# Sheet1.net
KiCad netlist of a schematic drawn in Altium Designer
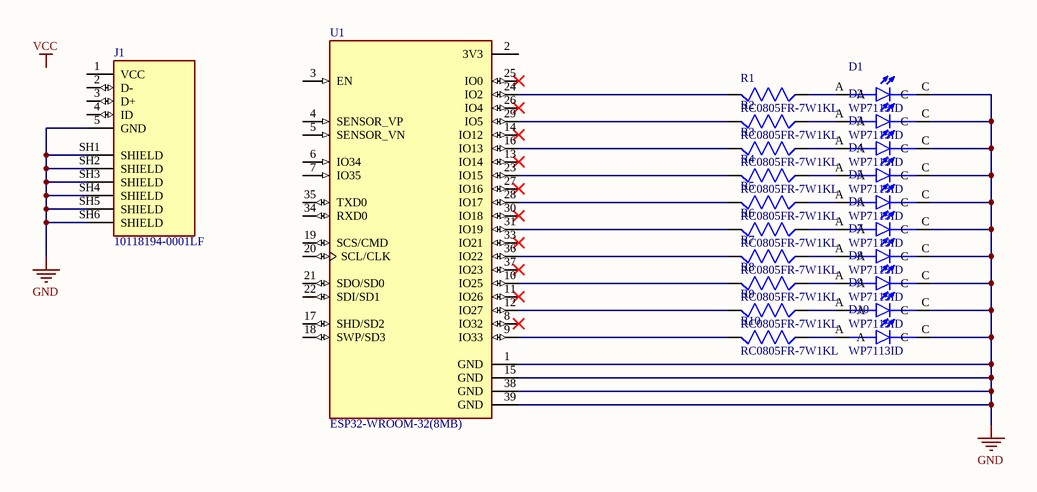
[diagram p0: Sheet1.SchDoc]

(export (version "E")
  (design (tool "Eeschema 10.0.6"))
  (components
    (comp (ref "D1")
      (value "WP7113ID")
      (footprint "LED_WP7113ID")
      (description "Red 617nm LED Indication - Discrete 2V Radial")
      (fields (field (name "MF") "Kingbright"))
      (libsource (lib "WP7113ID") (part "WP7113ID"))
    )
    (comp (ref "D2")
      (value "WP7113ID")
      (footprint "LED_WP7113ID")
      (description "Red 617nm LED Indication - Discrete 2V Radial")
      (fields (field (name "MF") "Kingbright"))
      (libsource (lib "WP7113ID") (part "WP7113ID"))
    )
    (comp (ref "D3")
      (value "WP7113ID")
      (footprint "LED_WP7113ID")
      (description "Red 617nm LED Indication - Discrete 2V Radial")
      (fields (field (name "MF") "Kingbright"))
      (libsource (lib "WP7113ID") (part "WP7113ID"))
    )
    (comp (ref "D4")
      (value "WP7113ID")
      (footprint "LED_WP7113ID")
      (description "Red 617nm LED Indication - Discrete 2V Radial")
      (fields (field (name "MF") "Kingbright"))
      (libsource (lib "WP7113ID") (part "WP7113ID"))
    )
    (comp (ref "D5")
      (value "WP7113ID")
      (footprint "LED_WP7113ID")
      (description "Red 617nm LED Indication - Discrete 2V Radial")
      (fields (field (name "MF") "Kingbright"))
      (libsource (lib "WP7113ID") (part "WP7113ID"))
    )
    (comp (ref "D6")
      (value "WP7113ID")
      (footprint "LED_WP7113ID")
      (description "Red 617nm LED Indication - Discrete 2V Radial")
      (fields (field (name "MF") "Kingbright"))
      (libsource (lib "WP7113ID") (part "WP7113ID"))
    )
    (comp (ref "D7")
      (value "WP7113ID")
      (footprint "LED_WP7113ID")
      (description "Red 617nm LED Indication - Discrete 2V Radial")
      (fields (field (name "MF") "Kingbright"))
      (libsource (lib "WP7113ID") (part "WP7113ID"))
    )
    (comp (ref "D8")
      (value "WP7113ID")
      (footprint "LED_WP7113ID")
      (description "Red 617nm LED Indication - Discrete 2V Radial")
      (fields (field (name "MF") "Kingbright"))
      (libsource (lib "WP7113ID") (part "WP7113ID"))
    )
    (comp (ref "D9")
      (value "WP7113ID")
      (footprint "LED_WP7113ID")
      (description "Red 617nm LED Indication - Discrete 2V Radial")
      (fields (field (name "MF") "Kingbright"))
      (libsource (lib "WP7113ID") (part "WP7113ID"))
    )
    (comp (ref "D10")
      (value "WP7113ID")
      (footprint "LED_WP7113ID")
      (description "Red 617nm LED Indication - Discrete 2V Radial")
      (fields (field (name "MF") "Kingbright"))
      (libsource (lib "WP7113ID") (part "WP7113ID"))
    )
    (comp (ref "J1")
      (value "10118194-0001LF")
      (footprint "AMPHENOL_10118194-0001LF")
      (description "Micro USB, Input Output Connectors, B TYPE RECEPTACLE with flange")
      (fields (field (name "MF") "Amphenol ICC"))
      (libsource (lib "10118194-0001LF") (part "10118194-0001LF"))
    )
    (comp (ref "R1")
      (value "RC0805FR-7W1KL")
      (footprint "RESC2012X60N")
      (libsource (lib "RC0805FR-7W1KL") (part "RC0805FR-7W1KL"))
    )
    (comp (ref "R2")
      (value "RC0805FR-7W1KL")
      (footprint "RESC2012X60N")
      (libsource (lib "RC0805FR-7W1KL") (part "RC0805FR-7W1KL"))
    )
    (comp (ref "R3")
      (value "RC0805FR-7W1KL")
      (footprint "RESC2012X60N")
      (libsource (lib "RC0805FR-7W1KL") (part "RC0805FR-7W1KL"))
    )
    (comp (ref "R4")
      (value "RC0805FR-7W1KL")
      (footprint "RESC2012X60N")
      (libsource (lib "RC0805FR-7W1KL") (part "RC0805FR-7W1KL"))
    )
    (comp (ref "R5")
      (value "RC0805FR-7W1KL")
      (footprint "RESC2012X60N")
      (libsource (lib "RC0805FR-7W1KL") (part "RC0805FR-7W1KL"))
    )
    (comp (ref "R6")
      (value "RC0805FR-7W1KL")
      (footprint "RESC2012X60N")
      (libsource (lib "RC0805FR-7W1KL") (part "RC0805FR-7W1KL"))
    )
    (comp (ref "R7")
      (value "RC0805FR-7W1KL")
      (footprint "RESC2012X60N")
      (libsource (lib "RC0805FR-7W1KL") (part "RC0805FR-7W1KL"))
    )
    (comp (ref "R8")
      (value "RC0805FR-7W1KL")
      (footprint "RESC2012X60N")
      (libsource (lib "RC0805FR-7W1KL") (part "RC0805FR-7W1KL"))
    )
    (comp (ref "R9")
      (value "RC0805FR-7W1KL")
      (footprint "RESC2012X60N")
      (libsource (lib "RC0805FR-7W1KL") (part "RC0805FR-7W1KL"))
    )
    (comp (ref "R10")
      (value "RC0805FR-7W1KL")
      (footprint "RESC2012X60N")
      (libsource (lib "RC0805FR-7W1KL") (part "RC0805FR-7W1KL"))
    )
    (comp (ref "U1")
      (value "ESP32-WROOM-32(8MB)")
      (footprint "MODULE_ESP32-WROOM-32(8MB)")
      (fields (field (name "MF") "Espressif Systems") (field (name "MP") "ESP32-WROOM-32 (8MB)"))
      (libsource (lib "ESP32-WROOM-32(8MB)") (part "ESP32-WROOM-32(8MB)"))
    )
  )
  (nets
    (net (code "1") (name "GND") (class "Default")
      (node (ref "D1") (pin "C") (pinfunction "C_C") (pintype "passive"))
      (node (ref "D10") (pin "C") (pinfunction "C_C") (pintype "passive"))
      (node (ref "D2") (pin "C") (pinfunction "C_C") (pintype "passive"))
      (node (ref "D3") (pin "C") (pinfunction "C_C") (pintype "passive"))
      (node (ref "D4") (pin "C") (pinfunction "C_C") (pintype "passive"))
      (node (ref "D5") (pin "C") (pinfunction "C_C") (pintype "passive"))
      (node (ref "D6") (pin "C") (pinfunction "C_C") (pintype "passive"))
      (node (ref "D7") (pin "C") (pinfunction "C_C") (pintype "passive"))
      (node (ref "D8") (pin "C") (pinfunction "C_C") (pintype "passive"))
      (node (ref "D9") (pin "C") (pinfunction "C_C") (pintype "passive"))
      (node (ref "J1") (pin "5") (pinfunction "GND_5") (pintype "power_in"))
      (node (ref "J1") (pin "SH1") (pinfunction "SHIELD_SH1") (pintype "passive"))
      (node (ref "J1") (pin "SH2") (pinfunction "SHIELD_SH2") (pintype "passive"))
      (node (ref "J1") (pin "SH3") (pinfunction "SHIELD_SH3") (pintype "passive"))
      (node (ref "J1") (pin "SH4") (pinfunction "SHIELD_SH4") (pintype "passive"))
      (node (ref "J1") (pin "SH5") (pinfunction "SHIELD_SH5") (pintype "passive"))
      (node (ref "J1") (pin "SH6") (pinfunction "SHIELD_SH6") (pintype "passive"))
      (node (ref "U1") (pin "1") (pinfunction "GND_1") (pintype "power_in"))
      (node (ref "U1") (pin "15") (pinfunction "GND_15") (pintype "power_in"))
      (node (ref "U1") (pin "38") (pinfunction "GND_38") (pintype "power_in"))
      (node (ref "U1") (pin "39") (pinfunction "GND_39") (pintype "power_in"))
    )
    (net (code "2") (name "Net-(D1-PadA)") (class "Default")
      (node (ref "D1") (pin "A") (pinfunction "A_A") (pintype "passive"))
      (node (ref "R1") (pin "2") (pinfunction "2_2") (pintype "passive"))
    )
    (net (code "3") (name "Net-(D2-PadA)") (class "Default")
      (node (ref "D2") (pin "A") (pinfunction "A_A") (pintype "passive"))
      (node (ref "R2") (pin "2") (pinfunction "2_2") (pintype "passive"))
    )
    (net (code "4") (name "Net-(D3-PadA)") (class "Default")
      (node (ref "D3") (pin "A") (pinfunction "A_A") (pintype "passive"))
      (node (ref "R3") (pin "2") (pinfunction "2_2") (pintype "passive"))
    )
    (net (code "5") (name "Net-(D4-PadA)") (class "Default")
      (node (ref "D4") (pin "A") (pinfunction "A_A") (pintype "passive"))
      (node (ref "R4") (pin "2") (pinfunction "2_2") (pintype "passive"))
    )
    (net (code "6") (name "Net-(D5-PadA)") (class "Default")
      (node (ref "D5") (pin "A") (pinfunction "A_A") (pintype "passive"))
      (node (ref "R5") (pin "2") (pinfunction "2_2") (pintype "passive"))
    )
    (net (code "7") (name "Net-(D6-PadA)") (class "Default")
      (node (ref "D6") (pin "A") (pinfunction "A_A") (pintype "passive"))
      (node (ref "R6") (pin "2") (pinfunction "2_2") (pintype "passive"))
    )
    (net (code "8") (name "Net-(D7-PadA)") (class "Default")
      (node (ref "D7") (pin "A") (pinfunction "A_A") (pintype "passive"))
      (node (ref "R7") (pin "2") (pinfunction "2_2") (pintype "passive"))
    )
    (net (code "9") (name "Net-(D8-PadA)") (class "Default")
      (node (ref "D8") (pin "A") (pinfunction "A_A") (pintype "passive"))
      (node (ref "R8") (pin "2") (pinfunction "2_2") (pintype "passive"))
    )
    (net (code "10") (name "Net-(D9-PadA)") (class "Default")
      (node (ref "D9") (pin "A") (pinfunction "A_A") (pintype "passive"))
      (node (ref "R9") (pin "2") (pinfunction "2_2") (pintype "passive"))
    )
    (net (code "11") (name "Net-(D10-PadA)") (class "Default")
      (node (ref "D10") (pin "A") (pinfunction "A_A") (pintype "passive"))
      (node (ref "R10") (pin "2") (pinfunction "2_2") (pintype "passive"))
    )
    (net (code "12") (name "Net-(U1-IO2)") (class "Default")
      (node (ref "R1") (pin "1") (pinfunction "1_1") (pintype "passive"))
      (node (ref "U1") (pin "24") (pinfunction "IO2_24") (pintype "bidirectional"))
    )
    (net (code "13") (name "Net-(U1-IO5)") (class "Default")
      (node (ref "R2") (pin "1") (pinfunction "1_1") (pintype "passive"))
      (node (ref "U1") (pin "29") (pinfunction "IO5_29") (pintype "bidirectional"))
    )
    (net (code "14") (name "Net-(U1-IO13)") (class "Default")
      (node (ref "R3") (pin "1") (pinfunction "1_1") (pintype "passive"))
      (node (ref "U1") (pin "16") (pinfunction "IO13_16") (pintype "bidirectional"))
    )
    (net (code "15") (name "Net-(U1-IO15)") (class "Default")
      (node (ref "R4") (pin "1") (pinfunction "1_1") (pintype "passive"))
      (node (ref "U1") (pin "23") (pinfunction "IO15_23") (pintype "bidirectional"))
    )
    (net (code "16") (name "Net-(U1-IO17)") (class "Default")
      (node (ref "R5") (pin "1") (pinfunction "1_1") (pintype "passive"))
      (node (ref "U1") (pin "28") (pinfunction "IO17_28") (pintype "bidirectional"))
    )
    (net (code "17") (name "Net-(U1-IO19)") (class "Default")
      (node (ref "R6") (pin "1") (pinfunction "1_1") (pintype "passive"))
      (node (ref "U1") (pin "31") (pinfunction "IO19_31") (pintype "bidirectional"))
    )
    (net (code "18") (name "Net-(U1-IO22)") (class "Default")
      (node (ref "R7") (pin "1") (pinfunction "1_1") (pintype "passive"))
      (node (ref "U1") (pin "36") (pinfunction "IO22_36") (pintype "bidirectional"))
    )
    (net (code "19") (name "Net-(U1-IO25)") (class "Default")
      (node (ref "R8") (pin "1") (pinfunction "1_1") (pintype "passive"))
      (node (ref "U1") (pin "10") (pinfunction "IO25_10") (pintype "bidirectional"))
    )
    (net (code "20") (name "Net-(U1-IO27)") (class "Default")
      (node (ref "R9") (pin "1") (pinfunction "1_1") (pintype "passive"))
      (node (ref "U1") (pin "12") (pinfunction "IO27_12") (pintype "bidirectional"))
    )
    (net (code "21") (name "Net-(U1-IO33)") (class "Default")
      (node (ref "R10") (pin "1") (pinfunction "1_1") (pintype "passive"))
      (node (ref "U1") (pin "9") (pinfunction "IO33_9") (pintype "bidirectional"))
    )
    (net (code "23") (name "unconnected-(J1-D+-Pad3)") (class "Default")
      (node (ref "J1") (pin "3") (pinfunction "D+_3") (pintype "bidirectional"))
    )
    (net (code "24") (name "unconnected-(J1-D--Pad2)") (class "Default")
      (node (ref "J1") (pin "2") (pinfunction "D-_2") (pintype "bidirectional"))
    )
    (net (code "25") (name "unconnected-(J1-ID-Pad4)") (class "Default")
      (node (ref "J1") (pin "4") (pinfunction "ID_4") (pintype "bidirectional"))
    )
    (net (code "26") (name "unconnected-(J1-VCC-Pad1)") (class "Default")
      (node (ref "J1") (pin "1") (pinfunction "VCC_1") (pintype "power_in"))
    )
    (net (code "27") (name "unconnected-(U1-3V3-Pad2)") (class "Default")
      (node (ref "U1") (pin "2") (pinfunction "3V3_2") (pintype "power_in"))
    )
    (net (code "28") (name "unconnected-(U1-EN-Pad3)") (class "Default")
      (node (ref "U1") (pin "3") (pinfunction "EN_3") (pintype "input"))
    )
    (net (code "29") (name "unconnected-(U1-IO0-Pad25)") (class "Default")
      (node (ref "U1") (pin "25") (pinfunction "IO0_25") (pintype "bidirectional+no_connect"))
    )
    (net (code "30") (name "unconnected-(U1-IO4-Pad26)") (class "Default")
      (node (ref "U1") (pin "26") (pinfunction "IO4_26") (pintype "bidirectional+no_connect"))
    )
    (net (code "31") (name "unconnected-(U1-IO12-Pad14)") (class "Default")
      (node (ref "U1") (pin "14") (pinfunction "IO12_14") (pintype "bidirectional+no_connect"))
    )
    (net (code "32") (name "unconnected-(U1-IO14-Pad13)") (class "Default")
      (node (ref "U1") (pin "13") (pinfunction "IO14_13") (pintype "bidirectional+no_connect"))
    )
    (net (code "33") (name "unconnected-(U1-IO16-Pad27)") (class "Default")
      (node (ref "U1") (pin "27") (pinfunction "IO16_27") (pintype "bidirectional+no_connect"))
    )
    (net (code "34") (name "unconnected-(U1-IO18-Pad30)") (class "Default")
      (node (ref "U1") (pin "30") (pinfunction "IO18_30") (pintype "bidirectional+no_connect"))
    )
    (net (code "35") (name "unconnected-(U1-IO21-Pad33)") (class "Default")
      (node (ref "U1") (pin "33") (pinfunction "IO21_33") (pintype "bidirectional+no_connect"))
    )
    (net (code "36") (name "unconnected-(U1-IO23-Pad37)") (class "Default")
      (node (ref "U1") (pin "37") (pinfunction "IO23_37") (pintype "bidirectional+no_connect"))
    )
    (net (code "37") (name "unconnected-(U1-IO26-Pad11)") (class "Default")
      (node (ref "U1") (pin "11") (pinfunction "IO26_11") (pintype "bidirectional+no_connect"))
    )
    (net (code "38") (name "unconnected-(U1-IO32-Pad8)") (class "Default")
      (node (ref "U1") (pin "8") (pinfunction "IO32_8") (pintype "bidirectional+no_connect"))
    )
    (net (code "39") (name "unconnected-(U1-IO34-Pad6)") (class "Default")
      (node (ref "U1") (pin "6") (pinfunction "IO34_6") (pintype "input"))
    )
    (net (code "40") (name "unconnected-(U1-IO35-Pad7)") (class "Default")
      (node (ref "U1") (pin "7") (pinfunction "IO35_7") (pintype "input"))
    )
    (net (code "41") (name "unconnected-(U1-RXD0-Pad34)") (class "Default")
      (node (ref "U1") (pin "34") (pinfunction "RXD0_34") (pintype "bidirectional"))
    )
    (net (code "42") (name "unconnected-(U1-SCL{slash}CLK-Pad20)") (class "Default")
      (node (ref "U1") (pin "20") (pinfunction "SCL/CLK_20") (pintype "bidirectional"))
    )
    (net (code "43") (name "unconnected-(U1-SCS{slash}CMD-Pad19)") (class "Default")
      (node (ref "U1") (pin "19") (pinfunction "SCS/CMD_19") (pintype "bidirectional"))
    )
    (net (code "44") (name "unconnected-(U1-SDI{slash}SD1-Pad22)") (class "Default")
      (node (ref "U1") (pin "22") (pinfunction "SDI/SD1_22") (pintype "bidirectional"))
    )
    (net (code "45") (name "unconnected-(U1-SDO{slash}SD0-Pad21)") (class "Default")
      (node (ref "U1") (pin "21") (pinfunction "SDO/SD0_21") (pintype "bidirectional"))
    )
    (net (code "46") (name "unconnected-(U1-SENSOR_VN-Pad5)") (class "Default")
      (node (ref "U1") (pin "5") (pinfunction "SENSOR_VN_5") (pintype "input"))
    )
    (net (code "47") (name "unconnected-(U1-SENSOR_VP-Pad4)") (class "Default")
      (node (ref "U1") (pin "4") (pinfunction "SENSOR_VP_4") (pintype "input"))
    )
    (net (code "48") (name "unconnected-(U1-SHD{slash}SD2-Pad17)") (class "Default")
      (node (ref "U1") (pin "17") (pinfunction "SHD/SD2_17") (pintype "bidirectional"))
    )
    (net (code "49") (name "unconnected-(U1-SWP{slash}SD3-Pad18)") (class "Default")
      (node (ref "U1") (pin "18") (pinfunction "SWP/SD3_18") (pintype "bidirectional"))
    )
    (net (code "50") (name "unconnected-(U1-TXD0-Pad35)") (class "Default")
      (node (ref "U1") (pin "35") (pinfunction "TXD0_35") (pintype "bidirectional"))
    )
  )
)
